# joystick-tact_breakout.net
KiCad netlist of a schematic drawn in EAGLE
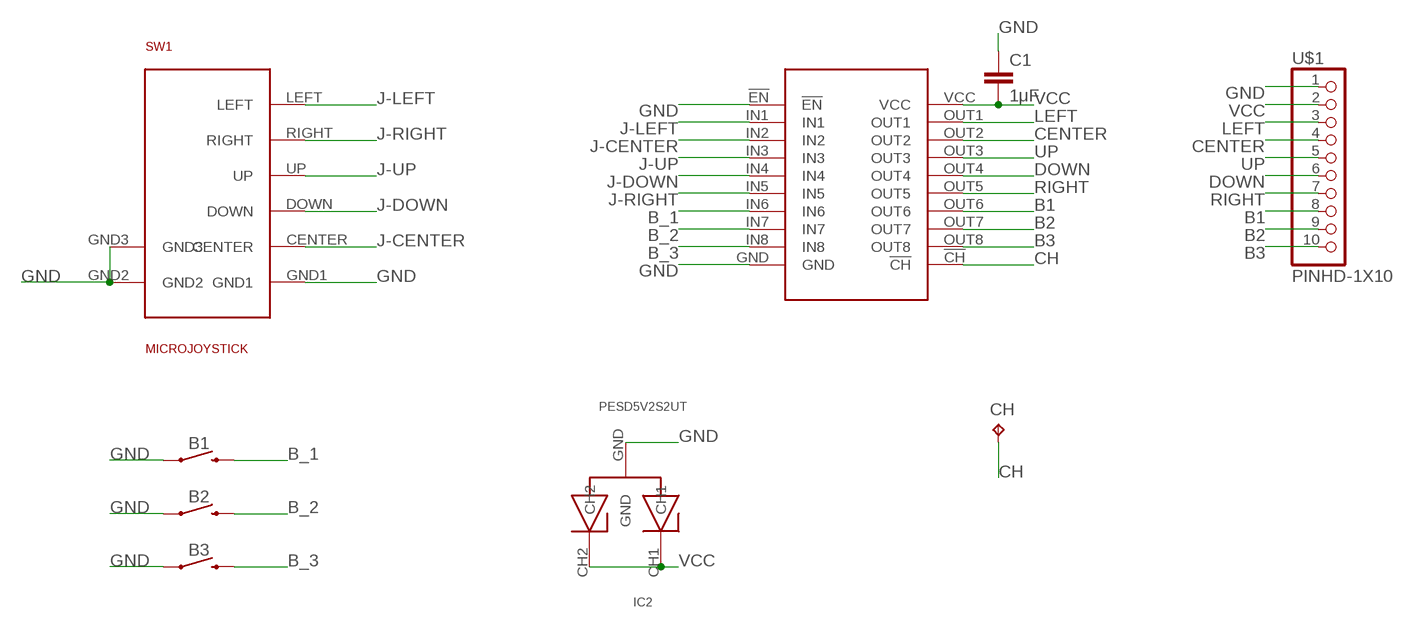
[diagram p0: schematic, sheet 1]

(export (version "E")
  (design (tool "Eeschema 10.0.6"))
  (components
    (comp (ref "B1")
      (value "MOMENTARY-SWITCH-SPST-SMD-4.5MM")
      (footprint "eagle-import:TACTILE_SWITCH_SMD_4.5MM")
      (libsource (lib "eagle-import") (part "MOMENTARY-SWITCH-SPST-SMD-4.5MM"))
    )
    (comp (ref "B2")
      (value "MOMENTARY-SWITCH-SPST-SMD-4.5MM")
      (footprint "eagle-import:TACTILE_SWITCH_SMD_4.5MM")
      (libsource (lib "eagle-import") (part "MOMENTARY-SWITCH-SPST-SMD-4.5MM"))
    )
    (comp (ref "B3")
      (value "MOMENTARY-SWITCH-SPST-SMD-4.5MM")
      (footprint "eagle-import:TACTILE_SWITCH_SMD_4.5MM")
      (libsource (lib "eagle-import") (part "MOMENTARY-SWITCH-SPST-SMD-4.5MM"))
    )
    (comp (ref "C1")
      (value "1μF")
      (footprint "eagle-import:C0805")
      (libsource (lib "eagle-import") (part "C-EUC0805"))
    )
    (comp (ref "CH")
      (value "TPB2,54")
      (footprint "eagle-import:B2,54")
      (libsource (lib "eagle-import") (part "TPB2,54"))
    )
    (comp (ref "IC1")
      (value "MAX6818")
      (footprint "eagle-import:TSSOP20")
      (libsource (lib "eagle-import") (part "MAX6818"))
    )
    (comp (ref "IC2")
      (value "PESD5V2S2UT")
      (footprint "eagle-import:SOT-23")
      (libsource (lib "eagle-import") (part "PESDXS2UT"))
    )
    (comp (ref "SW1")
      (value "MICROJOYSTICK")
      (footprint "eagle-import:MICROJOYSTICK")
      (libsource (lib "eagle-import") (part "MICROJOYSTICK"))
    )
    (comp (ref "U$1")
      (value "PINHD-1X10")
      (footprint "eagle-import:1X10-BIG")
      (libsource (lib "eagle-import") (part "PINHD-1X10"))
    )
  )
  (nets
    (net (code "1") (name "/B1") (class "Default")
      (node (ref "IC1") (pin "OUT6") (pinfunction "OUT6_OUT6") (pintype "bidirectional"))
      (node (ref "U$1") (pin "8") (pinfunction "8_8") (pintype "passive"))
    )
    (net (code "2") (name "/B2") (class "Default")
      (node (ref "IC1") (pin "OUT7") (pinfunction "OUT7_OUT7") (pintype "bidirectional"))
      (node (ref "U$1") (pin "9") (pinfunction "9_9") (pintype "passive"))
    )
    (net (code "3") (name "/B3") (class "Default")
      (node (ref "IC1") (pin "OUT8") (pinfunction "OUT8_OUT8") (pintype "bidirectional"))
      (node (ref "U$1") (pin "10") (pinfunction "10_10") (pintype "passive"))
    )
    (net (code "4") (name "/B_1") (class "Default")
      (node (ref "B1") (pin "1") (pinfunction "2_1") (pintype "passive"))
      (node (ref "B1") (pin "4") (pinfunction "2_4") (pintype "passive"))
      (node (ref "IC1") (pin "IN6") (pinfunction "IN6_IN6") (pintype "bidirectional"))
    )
    (net (code "5") (name "/B_2") (class "Default")
      (node (ref "B2") (pin "1") (pinfunction "2_1") (pintype "passive"))
      (node (ref "B2") (pin "4") (pinfunction "2_4") (pintype "passive"))
      (node (ref "IC1") (pin "IN7") (pinfunction "IN7_IN7") (pintype "bidirectional"))
    )
    (net (code "6") (name "/B_3") (class "Default")
      (node (ref "B3") (pin "1") (pinfunction "2_1") (pintype "passive"))
      (node (ref "B3") (pin "4") (pinfunction "2_4") (pintype "passive"))
      (node (ref "IC1") (pin "IN8") (pinfunction "IN8_IN8") (pintype "bidirectional"))
    )
    (net (code "7") (name "/CENTER") (class "Default")
      (node (ref "IC1") (pin "OUT2") (pinfunction "OUT2_OUT2") (pintype "bidirectional"))
      (node (ref "U$1") (pin "4") (pinfunction "4_4") (pintype "passive"))
    )
    (net (code "8") (name "/CH") (class "Default")
      (node (ref "CH") (pin "TP") (pinfunction "TP_TP") (pintype "input"))
      (node (ref "IC1") (pin "!CH!") (pinfunction "~{CH}_!CH!") (pintype "bidirectional"))
    )
    (net (code "9") (name "/DOWN") (class "Default")
      (node (ref "IC1") (pin "OUT4") (pinfunction "OUT4_OUT4") (pintype "bidirectional"))
      (node (ref "U$1") (pin "6") (pinfunction "6_6") (pintype "passive"))
    )
    (net (code "10") (name "/GND") (class "Default")
      (node (ref "B1") (pin "2") (pinfunction "1_2") (pintype "passive"))
      (node (ref "B1") (pin "3") (pinfunction "1_3") (pintype "passive"))
      (node (ref "B2") (pin "2") (pinfunction "1_2") (pintype "passive"))
      (node (ref "B2") (pin "3") (pinfunction "1_3") (pintype "passive"))
      (node (ref "B3") (pin "2") (pinfunction "1_2") (pintype "passive"))
      (node (ref "B3") (pin "3") (pinfunction "1_3") (pintype "passive"))
      (node (ref "C1") (pin "1") (pinfunction "1_1") (pintype "passive"))
      (node (ref "IC1") (pin "!EN!") (pinfunction "~{EN}_!EN!") (pintype "bidirectional"))
      (node (ref "IC1") (pin "GND") (pinfunction "GND_GND") (pintype "bidirectional"))
      (node (ref "IC2") (pin "GND") (pinfunction "GND_GND") (pintype "bidirectional"))
      (node (ref "SW1") (pin "GND1") (pinfunction "GND1_GND1") (pintype "bidirectional"))
      (node (ref "SW1") (pin "GND2") (pinfunction "GND2_GND2") (pintype "bidirectional"))
      (node (ref "SW1") (pin "GND3") (pinfunction "GND3_GND3") (pintype "bidirectional"))
      (node (ref "U$1") (pin "1") (pinfunction "1_1") (pintype "passive"))
    )
    (net (code "11") (name "/J-CENTER") (class "Default")
      (node (ref "IC1") (pin "IN2") (pinfunction "IN2_IN2") (pintype "bidirectional"))
      (node (ref "SW1") (pin "CENTER") (pinfunction "CENTER_CENTER") (pintype "bidirectional"))
    )
    (net (code "12") (name "/J-DOWN") (class "Default")
      (node (ref "IC1") (pin "IN4") (pinfunction "IN4_IN4") (pintype "bidirectional"))
      (node (ref "SW1") (pin "DOWN") (pinfunction "DOWN_DOWN") (pintype "bidirectional"))
    )
    (net (code "13") (name "/J-LEFT") (class "Default")
      (node (ref "IC1") (pin "IN1") (pinfunction "IN1_IN1") (pintype "bidirectional"))
      (node (ref "SW1") (pin "LEFT") (pinfunction "LEFT_LEFT") (pintype "bidirectional"))
    )
    (net (code "14") (name "/J-RIGHT") (class "Default")
      (node (ref "IC1") (pin "IN5") (pinfunction "IN5_IN5") (pintype "bidirectional"))
      (node (ref "SW1") (pin "RIGHT") (pinfunction "RIGHT_RIGHT") (pintype "bidirectional"))
    )
    (net (code "15") (name "/J-UP") (class "Default")
      (node (ref "IC1") (pin "IN3") (pinfunction "IN3_IN3") (pintype "bidirectional"))
      (node (ref "SW1") (pin "UP") (pinfunction "UP_UP") (pintype "bidirectional"))
    )
    (net (code "16") (name "/LEFT") (class "Default")
      (node (ref "IC1") (pin "OUT1") (pinfunction "OUT1_OUT1") (pintype "bidirectional"))
      (node (ref "U$1") (pin "3") (pinfunction "3_3") (pintype "passive"))
    )
    (net (code "17") (name "/RIGHT") (class "Default")
      (node (ref "IC1") (pin "OUT5") (pinfunction "OUT5_OUT5") (pintype "bidirectional"))
      (node (ref "U$1") (pin "7") (pinfunction "7_7") (pintype "passive"))
    )
    (net (code "18") (name "/UP") (class "Default")
      (node (ref "IC1") (pin "OUT3") (pinfunction "OUT3_OUT3") (pintype "bidirectional"))
      (node (ref "U$1") (pin "5") (pinfunction "5_5") (pintype "passive"))
    )
    (net (code "19") (name "/VCC") (class "Default")
      (node (ref "C1") (pin "2") (pinfunction "2_2") (pintype "passive"))
      (node (ref "IC1") (pin "VCC") (pinfunction "VCC_VCC") (pintype "bidirectional"))
      (node (ref "IC2") (pin "CH1") (pinfunction "CH1_CH1") (pintype "bidirectional"))
      (node (ref "IC2") (pin "CH2") (pinfunction "CH2_CH2") (pintype "bidirectional"))
      (node (ref "U$1") (pin "2") (pinfunction "2_2") (pintype "passive"))
    )
  )
)
